# SparkFun_Gyro_Breakout-LPY503AL.net
KiCad netlist of a schematic drawn in EAGLE
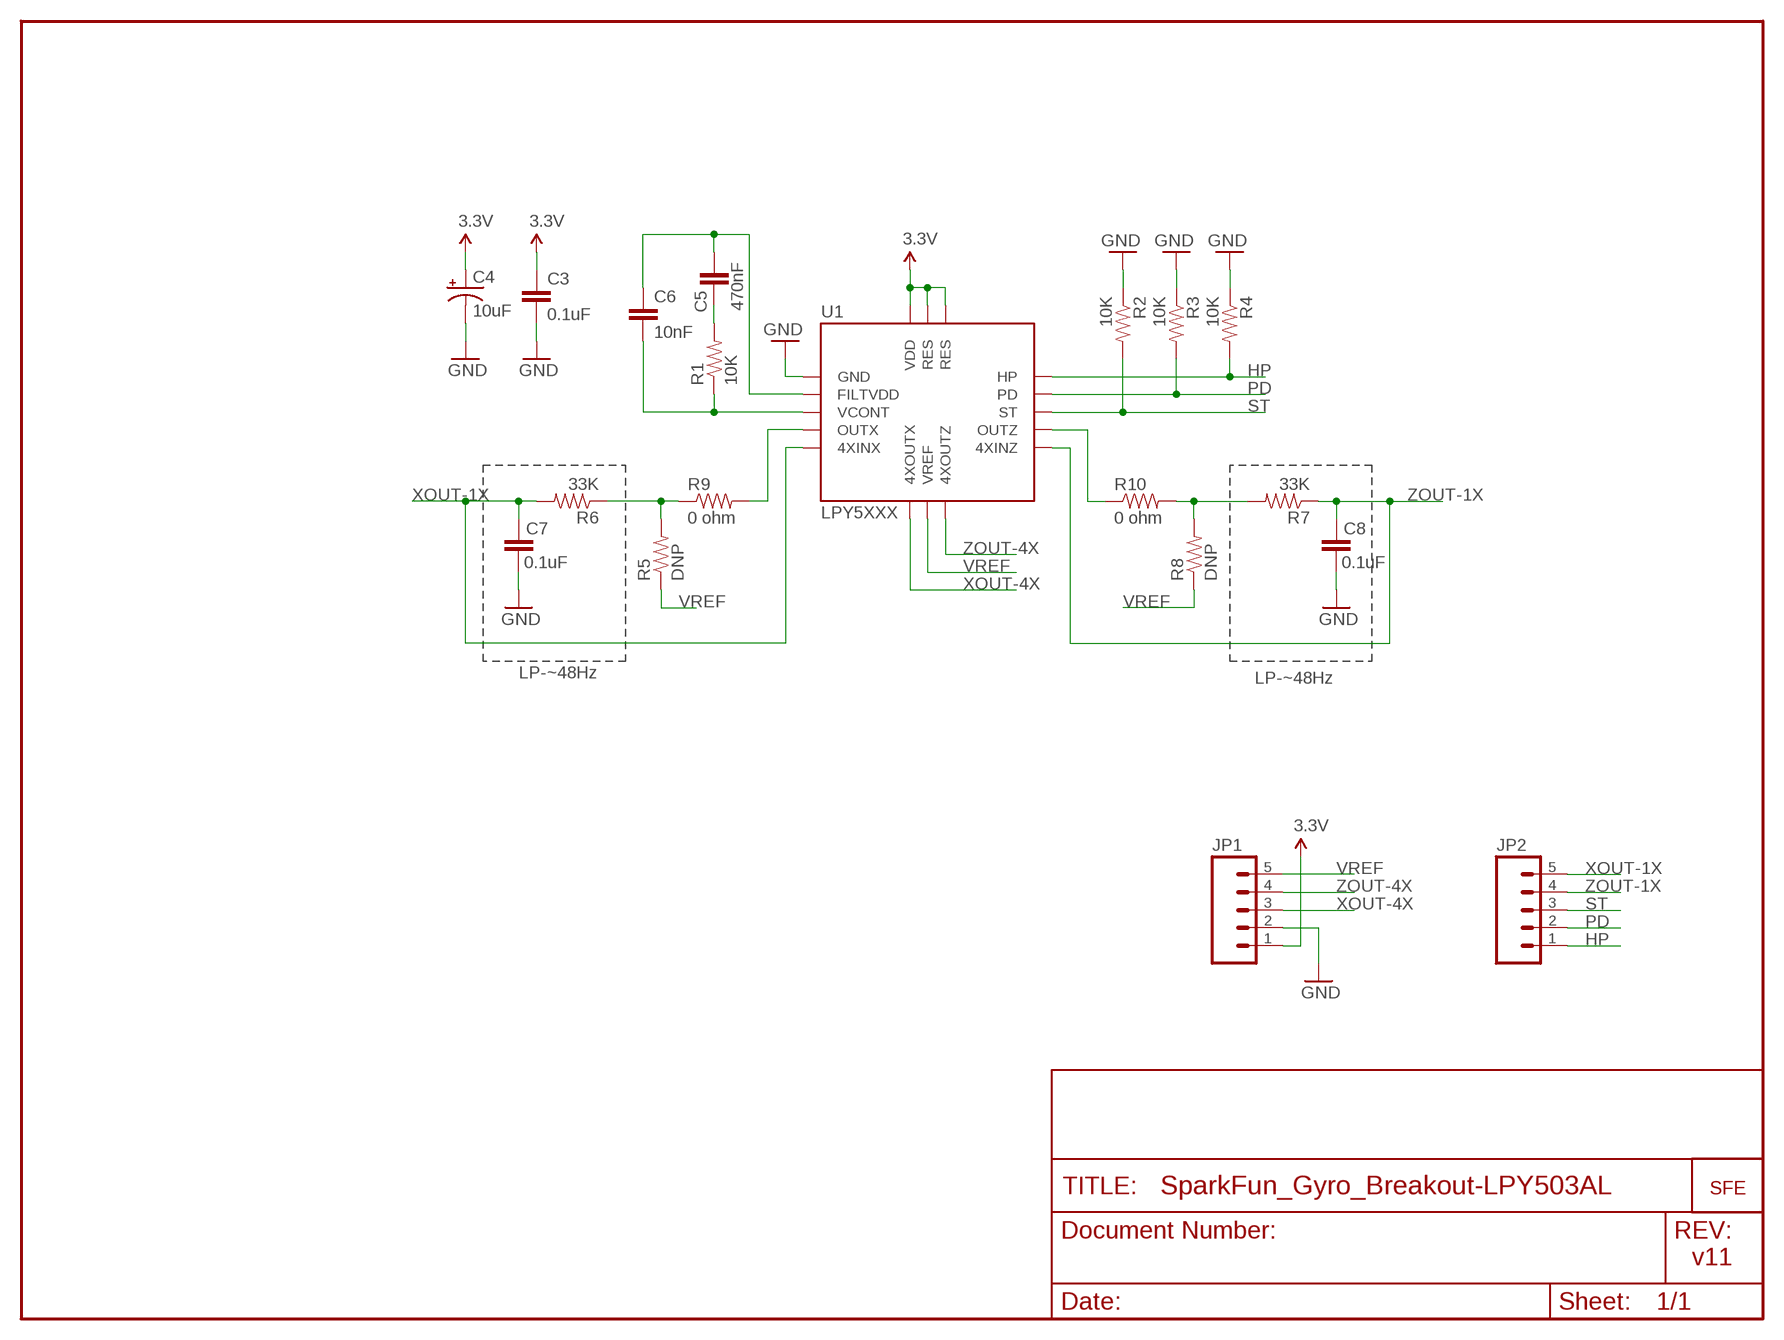
[diagram p0: schematic, sheet 1]

(export (version "E")
  (design (tool "Eeschema 10.0.6"))
  (components
    (comp (ref "C3")
      (value "0.1uF")
      (footprint "eagle-import:0402-CAP")
      (libsource (lib "eagle-import") (part "CAP0402-CAP"))
    )
    (comp (ref "C4")
      (value "10uF")
      (footprint "eagle-import:EIA3216")
      (libsource (lib "eagle-import") (part "CAP_POL1206"))
    )
    (comp (ref "C5")
      (value "470nF")
      (footprint "eagle-import:0402-CAP")
      (libsource (lib "eagle-import") (part "CAP0402-CAP"))
    )
    (comp (ref "C6")
      (value "10nF")
      (footprint "eagle-import:0402-CAP")
      (libsource (lib "eagle-import") (part "CAP0402-CAP"))
    )
    (comp (ref "C7")
      (value "0.1uF")
      (footprint "eagle-import:0402-CAP")
      (libsource (lib "eagle-import") (part "CAP0402-CAP"))
    )
    (comp (ref "C8")
      (value "0.1uF")
      (footprint "eagle-import:0402-CAP")
      (libsource (lib "eagle-import") (part "CAP0402-CAP"))
    )
    (comp (ref "JP1")
      (value "M05PTH")
      (footprint "eagle-import:1X05")
      (libsource (lib "eagle-import") (part "M05PTH"))
    )
    (comp (ref "JP2")
      (value "M05PTH")
      (footprint "eagle-import:1X05")
      (libsource (lib "eagle-import") (part "M05PTH"))
    )
    (comp (ref "R1")
      (value "10K")
      (footprint "eagle-import:0402-RES")
      (libsource (lib "eagle-import") (part "RESISTOR0402-RES"))
    )
    (comp (ref "R2")
      (value "10K")
      (footprint "eagle-import:0402-RES")
      (libsource (lib "eagle-import") (part "RESISTOR0402-RES"))
    )
    (comp (ref "R3")
      (value "10K")
      (footprint "eagle-import:0402-RES")
      (libsource (lib "eagle-import") (part "RESISTOR0402-RES"))
    )
    (comp (ref "R4")
      (value "10K")
      (footprint "eagle-import:0402-RES")
      (libsource (lib "eagle-import") (part "RESISTOR0402-RES"))
    )
    (comp (ref "R5")
      (value "DNP")
      (footprint "eagle-import:0402-RES")
      (libsource (lib "eagle-import") (part "RESISTOR0402-RES"))
    )
    (comp (ref "R6")
      (value "33K")
      (footprint "eagle-import:0402-RES")
      (libsource (lib "eagle-import") (part "RESISTOR0402-RES"))
    )
    (comp (ref "R7")
      (value "33K")
      (footprint "eagle-import:0402-RES")
      (libsource (lib "eagle-import") (part "RESISTOR0402-RES"))
    )
    (comp (ref "R8")
      (value "DNP")
      (footprint "eagle-import:0402-RES")
      (libsource (lib "eagle-import") (part "RESISTOR0402-RES"))
    )
    (comp (ref "R9")
      (value "0 ohm")
      (footprint "eagle-import:0402-RES")
      (libsource (lib "eagle-import") (part "RESISTOR0402-RES"))
    )
    (comp (ref "R10")
      (value "0 ohm")
      (footprint "eagle-import:0402-RES")
      (libsource (lib "eagle-import") (part "RESISTOR0402-RES"))
    )
    (comp (ref "U$1")
      (value "LOGO-SFESK")
      (footprint "eagle-import:SFE-LOGO-FLAME")
      (libsource (lib "eagle-import") (part "LOGO-SFESK"))
    )
    (comp (ref "U1")
      (value "LPY5XXX")
      (footprint "eagle-import:ST-GYRO")
      (libsource (lib "eagle-import") (part "ST-GYRO-PYSMD"))
    )
  )
  (nets
    (net (code "1") (name "/HP") (class "Default")
      (node (ref "JP2") (pin "1") (pinfunction "1_1") (pintype "passive"))
      (node (ref "R4") (pin "2") (pinfunction "2_2") (pintype "passive"))
      (node (ref "U1") (pin "13") (pinfunction "HP_13") (pintype "bidirectional"))
    )
    (net (code "2") (name "/PD") (class "Default")
      (node (ref "JP2") (pin "2") (pinfunction "2_2") (pintype "passive"))
      (node (ref "R3") (pin "2") (pinfunction "2_2") (pintype "passive"))
      (node (ref "U1") (pin "12") (pinfunction "PD_12") (pintype "bidirectional"))
    )
    (net (code "3") (name "/ST") (class "Default")
      (node (ref "JP2") (pin "3") (pinfunction "3_3") (pintype "passive"))
      (node (ref "R2") (pin "2") (pinfunction "2_2") (pintype "passive"))
      (node (ref "U1") (pin "11") (pinfunction "ST_11") (pintype "bidirectional"))
    )
    (net (code "4") (name "/VREF") (class "Default")
      (node (ref "JP1") (pin "5") (pinfunction "5_5") (pintype "passive"))
      (node (ref "R5") (pin "1") (pinfunction "1_1") (pintype "passive"))
      (node (ref "R8") (pin "1") (pinfunction "1_1") (pintype "passive"))
      (node (ref "U1") (pin "7") (pinfunction "VREF_7") (pintype "bidirectional"))
    )
    (net (code "5") (name "/XOUT-1X") (class "Default")
      (node (ref "C7") (pin "2") (pinfunction "2_2") (pintype "passive"))
      (node (ref "JP2") (pin "5") (pinfunction "5_5") (pintype "passive"))
      (node (ref "R6") (pin "2") (pinfunction "2_2") (pintype "passive"))
      (node (ref "U1") (pin "5") (pinfunction "4XINX_5") (pintype "bidirectional"))
    )
    (net (code "6") (name "/XOUT-4X") (class "Default")
      (node (ref "JP1") (pin "3") (pinfunction "3_3") (pintype "passive"))
      (node (ref "U1") (pin "6") (pinfunction "4XOUTX_6") (pintype "bidirectional"))
    )
    (net (code "7") (name "/ZOUT-1X") (class "Default")
      (node (ref "C8") (pin "2") (pinfunction "2_2") (pintype "passive"))
      (node (ref "JP2") (pin "4") (pinfunction "4_4") (pintype "passive"))
      (node (ref "R7") (pin "1") (pinfunction "1_1") (pintype "passive"))
      (node (ref "U1") (pin "9") (pinfunction "4XINZ_9") (pintype "bidirectional"))
    )
    (net (code "8") (name "/ZOUT-4X") (class "Default")
      (node (ref "JP1") (pin "4") (pinfunction "4_4") (pintype "passive"))
      (node (ref "U1") (pin "8") (pinfunction "4XOUTZ_8") (pintype "bidirectional"))
    )
    (net (code "9") (name "3.3V") (class "Default")
      (node (ref "C3") (pin "1") (pinfunction "1_1") (pintype "passive"))
      (node (ref "C4") (pin "A") (pinfunction "+_A") (pintype "passive"))
      (node (ref "JP1") (pin "1") (pinfunction "1_1") (pintype "passive"))
      (node (ref "U1") (pin "14") (pinfunction "RES_14") (pintype "bidirectional"))
      (node (ref "U1") (pin "15") (pinfunction "RES_15") (pintype "bidirectional"))
      (node (ref "U1") (pin "16") (pinfunction "VDD_16") (pintype "bidirectional"))
    )
    (net (code "10") (name "GND") (class "Default")
      (node (ref "C3") (pin "2") (pinfunction "2_2") (pintype "passive"))
      (node (ref "C4") (pin "C") (pinfunction "-_C") (pintype "passive"))
      (node (ref "C7") (pin "1") (pinfunction "1_1") (pintype "passive"))
      (node (ref "C8") (pin "1") (pinfunction "1_1") (pintype "passive"))
      (node (ref "JP1") (pin "2") (pinfunction "2_2") (pintype "passive"))
      (node (ref "R2") (pin "1") (pinfunction "1_1") (pintype "passive"))
      (node (ref "R3") (pin "1") (pinfunction "1_1") (pintype "passive"))
      (node (ref "R4") (pin "1") (pinfunction "1_1") (pintype "passive"))
      (node (ref "U1") (pin "1") (pinfunction "GND_1") (pintype "bidirectional"))
    )
    (net (code "11") (name "Net-(C5-Pad2)") (class "Default")
      (node (ref "C5") (pin "2") (pinfunction "2_2") (pintype "passive"))
      (node (ref "R1") (pin "2") (pinfunction "2_2") (pintype "passive"))
    )
    (net (code "12") (name "Net-(R5-Pad2)") (class "Default")
      (node (ref "R5") (pin "2") (pinfunction "2_2") (pintype "passive"))
      (node (ref "R6") (pin "1") (pinfunction "1_1") (pintype "passive"))
      (node (ref "R9") (pin "1") (pinfunction "1_1") (pintype "passive"))
    )
    (net (code "13") (name "Net-(R10-Pad2)") (class "Default")
      (node (ref "R10") (pin "2") (pinfunction "2_2") (pintype "passive"))
      (node (ref "R7") (pin "2") (pinfunction "2_2") (pintype "passive"))
      (node (ref "R8") (pin "2") (pinfunction "2_2") (pintype "passive"))
    )
    (net (code "14") (name "Net-(U1-FILTVDD)") (class "Default")
      (node (ref "C5") (pin "1") (pinfunction "1_1") (pintype "passive"))
      (node (ref "C6") (pin "1") (pinfunction "1_1") (pintype "passive"))
      (node (ref "U1") (pin "2") (pinfunction "FILTVDD_2") (pintype "bidirectional"))
    )
    (net (code "15") (name "Net-(U1-OUTX)") (class "Default")
      (node (ref "R9") (pin "2") (pinfunction "2_2") (pintype "passive"))
      (node (ref "U1") (pin "4") (pinfunction "OUTX_4") (pintype "bidirectional"))
    )
    (net (code "16") (name "Net-(U1-OUTZ)") (class "Default")
      (node (ref "R10") (pin "1") (pinfunction "1_1") (pintype "passive"))
      (node (ref "U1") (pin "10") (pinfunction "OUTZ_10") (pintype "bidirectional"))
    )
    (net (code "17") (name "Net-(U1-VCONT)") (class "Default")
      (node (ref "C6") (pin "2") (pinfunction "2_2") (pintype "passive"))
      (node (ref "R1") (pin "1") (pinfunction "1_1") (pintype "passive"))
      (node (ref "U1") (pin "3") (pinfunction "VCONT_3") (pintype "bidirectional"))
    )
  )
)
